# M105-bad.net
KiCad netlist of a schematic drawn in EAGLE
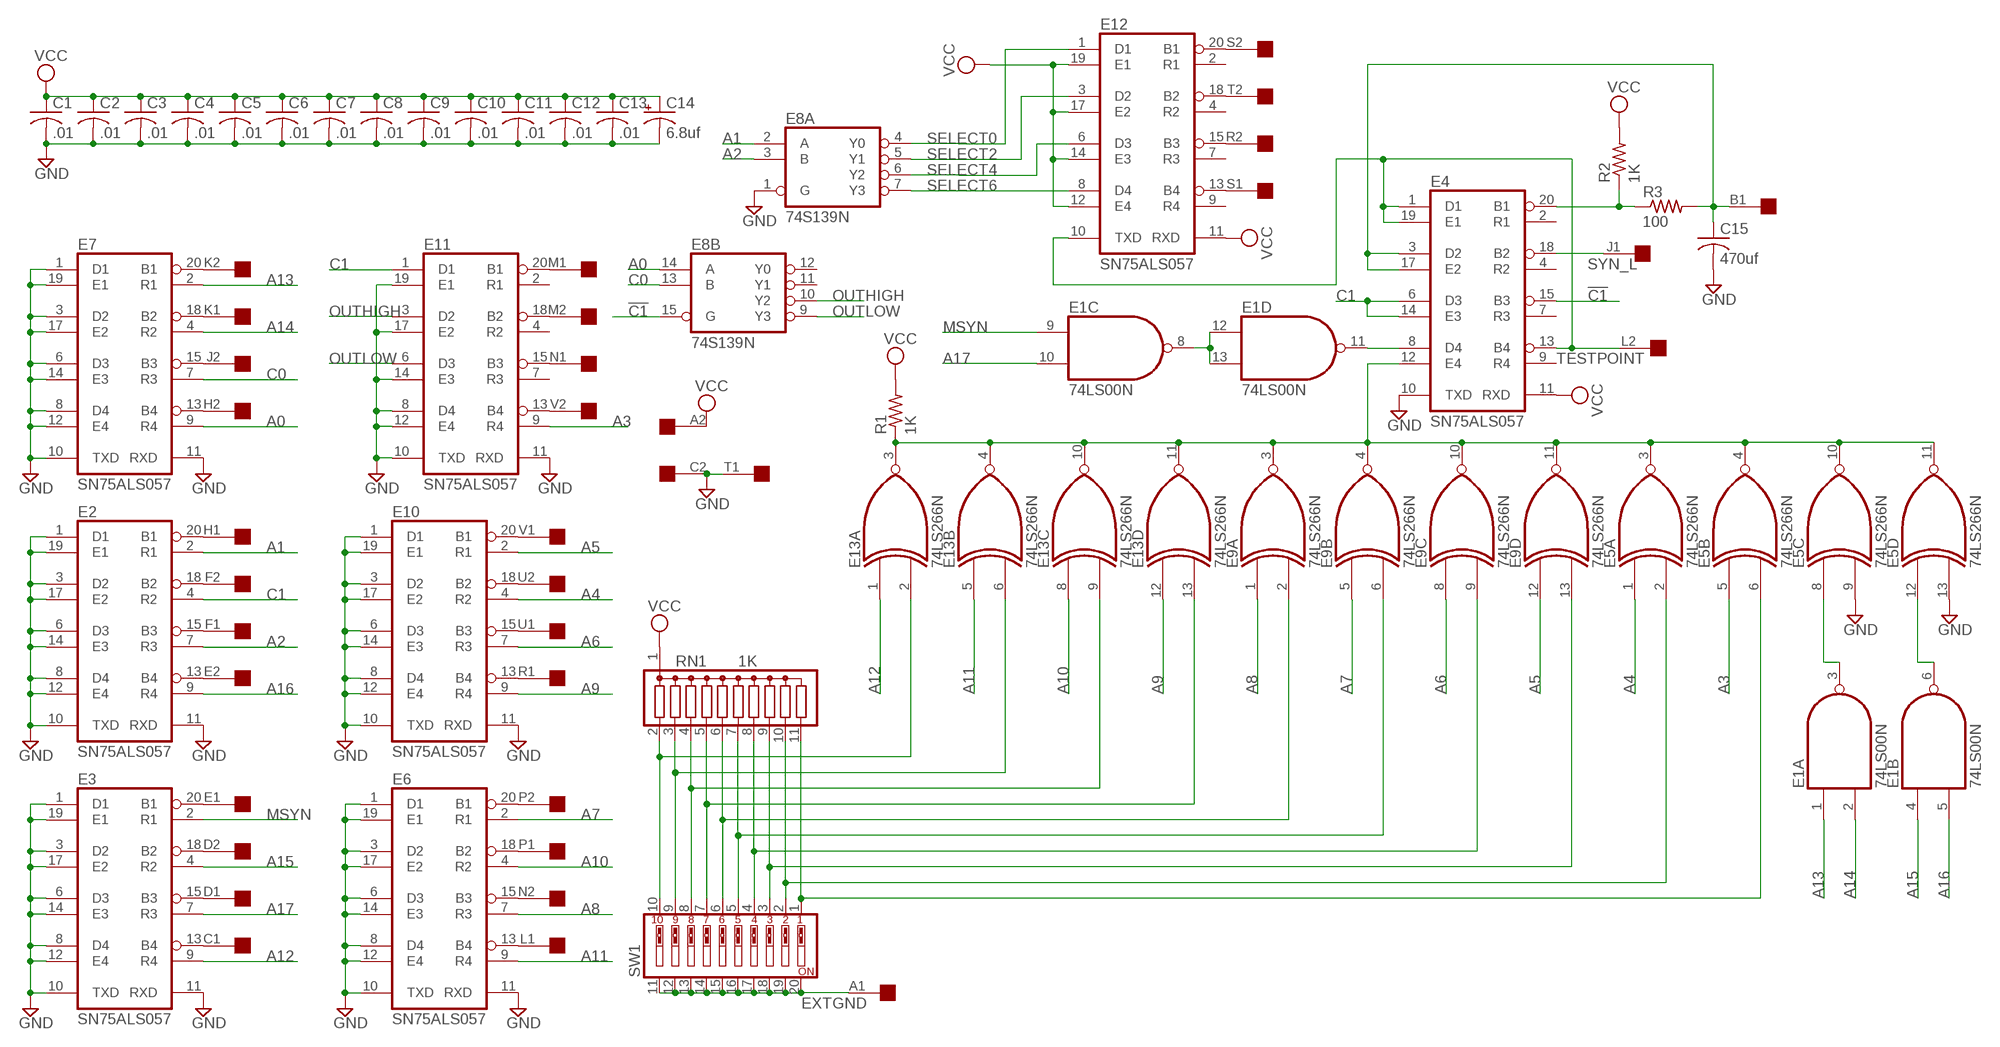
[diagram p0: schematic, sheet 1]

(export (version "E")
  (design (tool "Eeschema 10.0.6"))
  (components
    (comp (ref "C1")
      (value ".01")
      (footprint "eagle-import:C050-025X075")
      (libsource (lib "eagle-import") (part "C-US050-025X075"))
    )
    (comp (ref "C2")
      (value ".01")
      (footprint "eagle-import:C050-025X075")
      (libsource (lib "eagle-import") (part "C-US050-025X075"))
    )
    (comp (ref "C3")
      (value ".01")
      (footprint "eagle-import:C050-025X075")
      (libsource (lib "eagle-import") (part "C-US050-025X075"))
    )
    (comp (ref "C4")
      (value ".01")
      (footprint "eagle-import:C050-025X075")
      (libsource (lib "eagle-import") (part "C-US050-025X075"))
    )
    (comp (ref "C5")
      (value ".01")
      (footprint "eagle-import:C050-025X075")
      (libsource (lib "eagle-import") (part "C-US050-025X075"))
    )
    (comp (ref "C6")
      (value ".01")
      (footprint "eagle-import:C050-025X075")
      (libsource (lib "eagle-import") (part "C-US050-025X075"))
    )
    (comp (ref "C7")
      (value ".01")
      (footprint "eagle-import:C050-025X075")
      (libsource (lib "eagle-import") (part "C-US050-025X075"))
    )
    (comp (ref "C8")
      (value ".01")
      (footprint "eagle-import:C050-025X075")
      (libsource (lib "eagle-import") (part "C-US050-025X075"))
    )
    (comp (ref "C9")
      (value ".01")
      (footprint "eagle-import:C050-025X075")
      (libsource (lib "eagle-import") (part "C-US050-025X075"))
    )
    (comp (ref "C10")
      (value ".01")
      (footprint "eagle-import:C050-025X075")
      (libsource (lib "eagle-import") (part "C-US050-025X075"))
    )
    (comp (ref "C11")
      (value ".01")
      (footprint "eagle-import:C050-025X075")
      (libsource (lib "eagle-import") (part "C-US050-025X075"))
    )
    (comp (ref "C12")
      (value ".01")
      (footprint "eagle-import:C050-025X075")
      (libsource (lib "eagle-import") (part "C-US050-025X075"))
    )
    (comp (ref "C13")
      (value ".01")
      (footprint "eagle-import:C050-025X075")
      (libsource (lib "eagle-import") (part "C-US050-025X075"))
    )
    (comp (ref "C14")
      (value "6.8uf")
      (footprint "eagle-import:E15-5")
      (libsource (lib "eagle-import") (part "CPOL-USE15-5AXIAL"))
    )
    (comp (ref "C15")
      (value "470uf")
      (footprint "eagle-import:C050-025X075")
      (libsource (lib "eagle-import") (part "C-US050-025X075"))
    )
    (comp (ref "E1")
      (value "74LS00N")
      (footprint "eagle-import:DIL14")
      (libsource (lib "eagle-import") (part "7400NLS"))
    )
    (comp (ref "E2")
      (value "SN75ALS057")
      (footprint "eagle-import:DIL20")
      (libsource (lib "eagle-import") (part "SN75ALS057"))
    )
    (comp (ref "E3")
      (value "SN75ALS057")
      (footprint "eagle-import:DIL20")
      (libsource (lib "eagle-import") (part "SN75ALS057"))
    )
    (comp (ref "E4")
      (value "SN75ALS057")
      (footprint "eagle-import:DIL20")
      (libsource (lib "eagle-import") (part "SN75ALS057"))
    )
    (comp (ref "E5")
      (value "74LS266N")
      (footprint "eagle-import:DIL14")
      (libsource (lib "eagle-import") (part "74266NLS"))
    )
    (comp (ref "E6")
      (value "SN75ALS057")
      (footprint "eagle-import:DIL20")
      (libsource (lib "eagle-import") (part "SN75ALS057"))
    )
    (comp (ref "E7")
      (value "SN75ALS057")
      (footprint "eagle-import:DIL20")
      (libsource (lib "eagle-import") (part "SN75ALS057"))
    )
    (comp (ref "E8")
      (value "74S139N")
      (footprint "eagle-import:DIL16")
      (libsource (lib "eagle-import") (part "74139NS"))
    )
    (comp (ref "E9")
      (value "74LS266N")
      (footprint "eagle-import:DIL14")
      (libsource (lib "eagle-import") (part "74266NLS"))
    )
    (comp (ref "E10")
      (value "SN75ALS057")
      (footprint "eagle-import:DIL20")
      (libsource (lib "eagle-import") (part "SN75ALS057"))
    )
    (comp (ref "E11")
      (value "SN75ALS057")
      (footprint "eagle-import:DIL20")
      (libsource (lib "eagle-import") (part "SN75ALS057"))
    )
    (comp (ref "E12")
      (value "SN75ALS057")
      (footprint "eagle-import:DIL20")
      (libsource (lib "eagle-import") (part "SN75ALS057"))
    )
    (comp (ref "E13")
      (value "74LS266N")
      (footprint "eagle-import:DIL14")
      (libsource (lib "eagle-import") (part "74266NLS"))
    )
    (comp (ref "R1")
      (value "1K")
      (footprint "eagle-import:0207_10")
      (libsource (lib "eagle-import") (part "R-US_0207/10"))
    )
    (comp (ref "R2")
      (value "1K")
      (footprint "eagle-import:0207_10")
      (libsource (lib "eagle-import") (part "R-US_0207/10"))
    )
    (comp (ref "R3")
      (value "100")
      (footprint "eagle-import:0207_10")
      (libsource (lib "eagle-import") (part "R-US_0207/10"))
    )
    (comp (ref "RN1")
      (value "1K")
      (footprint "eagle-import:SIL11")
      (libsource (lib "eagle-import") (part "G10R"))
    )
    (comp (ref "SW1")
      (value "SW_DIP-10")
      (footprint "eagle-import:EDG-10")
      (libsource (lib "eagle-import") (part "SW_DIP-10"))
    )
    (comp (ref "U$1")
      (value "SINGLE")
      (footprint "eagle-import:EDGE-CON2")
      (libsource (lib "eagle-import") (part "SINGLE"))
    )
  )
  (nets
    (net (code "1") (name "/A0") (class "Default")
      (node (ref "E7") (pin "9") (pinfunction "R4_9") (pintype "output"))
      (node (ref "E8") (pin "14") (pinfunction "A_14") (pintype "input"))
    )
    (net (code "2") (name "/A1") (class "Default")
      (node (ref "E2") (pin "2") (pinfunction "R1_2") (pintype "output"))
      (node (ref "E8") (pin "2") (pinfunction "A_2") (pintype "input"))
    )
    (net (code "3") (name "/A2") (class "Default")
      (node (ref "E2") (pin "7") (pinfunction "R3_7") (pintype "output"))
      (node (ref "E8") (pin "3") (pinfunction "B_3") (pintype "input"))
    )
    (net (code "4") (name "/A3") (class "Default")
      (node (ref "E11") (pin "9") (pinfunction "R4_9") (pintype "output"))
      (node (ref "E5") (pin "5") (pinfunction "I0_5") (pintype "input"))
    )
    (net (code "5") (name "/A4") (class "Default")
      (node (ref "E10") (pin "4") (pinfunction "R2_4") (pintype "output"))
      (node (ref "E5") (pin "1") (pinfunction "I0_1") (pintype "input"))
    )
    (net (code "6") (name "/A5") (class "Default")
      (node (ref "E10") (pin "2") (pinfunction "R1_2") (pintype "output"))
      (node (ref "E9") (pin "12") (pinfunction "I0_12") (pintype "input"))
    )
    (net (code "7") (name "/A6") (class "Default")
      (node (ref "E10") (pin "7") (pinfunction "R3_7") (pintype "output"))
      (node (ref "E9") (pin "8") (pinfunction "I0_8") (pintype "input"))
    )
    (net (code "8") (name "/A7") (class "Default")
      (node (ref "E6") (pin "2") (pinfunction "R1_2") (pintype "output"))
      (node (ref "E9") (pin "5") (pinfunction "I0_5") (pintype "input"))
    )
    (net (code "9") (name "/A8") (class "Default")
      (node (ref "E6") (pin "7") (pinfunction "R3_7") (pintype "output"))
      (node (ref "E9") (pin "1") (pinfunction "I0_1") (pintype "input"))
    )
    (net (code "10") (name "/A9") (class "Default")
      (node (ref "E10") (pin "9") (pinfunction "R4_9") (pintype "output"))
      (node (ref "E13") (pin "12") (pinfunction "I0_12") (pintype "input"))
    )
    (net (code "11") (name "/A10") (class "Default")
      (node (ref "E13") (pin "8") (pinfunction "I0_8") (pintype "input"))
      (node (ref "E6") (pin "4") (pinfunction "R2_4") (pintype "output"))
    )
    (net (code "12") (name "/A11") (class "Default")
      (node (ref "E13") (pin "5") (pinfunction "I0_5") (pintype "input"))
      (node (ref "E6") (pin "9") (pinfunction "R4_9") (pintype "output"))
    )
    (net (code "13") (name "/A12") (class "Default")
      (node (ref "E13") (pin "1") (pinfunction "I0_1") (pintype "input"))
      (node (ref "E3") (pin "9") (pinfunction "R4_9") (pintype "output"))
    )
    (net (code "14") (name "/A13") (class "Default")
      (node (ref "E1") (pin "1") (pinfunction "I0_1") (pintype "input"))
      (node (ref "E7") (pin "2") (pinfunction "R1_2") (pintype "output"))
    )
    (net (code "15") (name "/A14") (class "Default")
      (node (ref "E1") (pin "2") (pinfunction "I1_2") (pintype "input"))
      (node (ref "E7") (pin "4") (pinfunction "R2_4") (pintype "output"))
    )
    (net (code "16") (name "/A15") (class "Default")
      (node (ref "E1") (pin "4") (pinfunction "I0_4") (pintype "input"))
      (node (ref "E3") (pin "4") (pinfunction "R2_4") (pintype "output"))
    )
    (net (code "17") (name "/A16") (class "Default")
      (node (ref "E1") (pin "5") (pinfunction "I1_5") (pintype "input"))
      (node (ref "E2") (pin "9") (pinfunction "R4_9") (pintype "output"))
    )
    (net (code "18") (name "/A17") (class "Default")
      (node (ref "E1") (pin "10") (pinfunction "I1_10") (pintype "input"))
      (node (ref "E3") (pin "7") (pinfunction "R3_7") (pintype "output"))
    )
    (net (code "19") (name "/C0") (class "Default")
      (node (ref "E7") (pin "7") (pinfunction "R3_7") (pintype "output"))
      (node (ref "E8") (pin "13") (pinfunction "B_13") (pintype "input"))
    )
    (net (code "20") (name "/C1") (class "Default")
      (node (ref "E11") (pin "1") (pinfunction "D1_1") (pintype "input"))
      (node (ref "E2") (pin "4") (pinfunction "R2_4") (pintype "output"))
      (node (ref "E4") (pin "14") (pinfunction "E3_14") (pintype "input"))
      (node (ref "E4") (pin "6") (pinfunction "D3_6") (pintype "input"))
    )
    (net (code "21") (name "/EXTGND") (class "Default")
      (node (ref "SW1") (pin "11") (pinfunction "11_11") (pintype "passive"))
      (node (ref "SW1") (pin "12") (pinfunction "12_12") (pintype "passive"))
      (node (ref "SW1") (pin "13") (pinfunction "13_13") (pintype "passive"))
      (node (ref "SW1") (pin "14") (pinfunction "14_14") (pintype "passive"))
      (node (ref "SW1") (pin "15") (pinfunction "15_15") (pintype "passive"))
      (node (ref "SW1") (pin "16") (pinfunction "16_16") (pintype "passive"))
      (node (ref "SW1") (pin "17") (pinfunction "17_17") (pintype "passive"))
      (node (ref "SW1") (pin "18") (pinfunction "18_18") (pintype "passive"))
      (node (ref "SW1") (pin "19") (pinfunction "19_19") (pintype "passive"))
      (node (ref "SW1") (pin "20") (pinfunction "20_20") (pintype "passive"))
      (node (ref "U$1") (pin "A1") (pinfunction "1_A1") (pintype "bidirectional"))
    )
    (net (code "22") (name "/MSYN") (class "Default")
      (node (ref "E1") (pin "9") (pinfunction "I0_9") (pintype "input"))
      (node (ref "E3") (pin "2") (pinfunction "R1_2") (pintype "output"))
    )
    (net (code "23") (name "/OUTHIGH") (class "Default")
      (node (ref "E11") (pin "3") (pinfunction "D2_3") (pintype "input"))
      (node (ref "E8") (pin "10") (pinfunction "Y2_10") (pintype "output"))
    )
    (net (code "24") (name "/OUTLOW") (class "Default")
      (node (ref "E11") (pin "6") (pinfunction "D3_6") (pintype "input"))
      (node (ref "E8") (pin "9") (pinfunction "Y3_9") (pintype "output"))
    )
    (net (code "25") (name "/SELECT0") (class "Default")
      (node (ref "E12") (pin "1") (pinfunction "D1_1") (pintype "input"))
      (node (ref "E8") (pin "4") (pinfunction "Y0_4") (pintype "output"))
    )
    (net (code "26") (name "/SELECT2") (class "Default")
      (node (ref "E12") (pin "3") (pinfunction "D2_3") (pintype "input"))
      (node (ref "E8") (pin "5") (pinfunction "Y1_5") (pintype "output"))
    )
    (net (code "27") (name "/SELECT4") (class "Default")
      (node (ref "E12") (pin "6") (pinfunction "D3_6") (pintype "input"))
      (node (ref "E8") (pin "6") (pinfunction "Y2_6") (pintype "output"))
    )
    (net (code "28") (name "/SELECT6") (class "Default")
      (node (ref "E12") (pin "8") (pinfunction "D4_8") (pintype "input"))
      (node (ref "E8") (pin "7") (pinfunction "Y3_7") (pintype "output"))
    )
    (net (code "29") (name "/SYN_L") (class "Default")
      (node (ref "E4") (pin "18") (pinfunction "B2_18") (pintype "bidirectional"))
      (node (ref "U$1") (pin "J1") (pinfunction "1_J1") (pintype "bidirectional"))
    )
    (net (code "30") (name "/TESTPOINT") (class "Default")
      (node (ref "E12") (pin "10") (pinfunction "TXD_10") (pintype "input"))
      (node (ref "E4") (pin "1") (pinfunction "D1_1") (pintype "input"))
      (node (ref "E4") (pin "13") (pinfunction "B4_13") (pintype "bidirectional"))
      (node (ref "E4") (pin "19") (pinfunction "E1_19") (pintype "input"))
      (node (ref "U$1") (pin "L2") (pinfunction "1_L2") (pintype "bidirectional"))
    )
    (net (code "31") (name "/~{C1}") (class "Default")
      (node (ref "E4") (pin "15") (pinfunction "B3_15") (pintype "bidirectional"))
      (node (ref "E8") (pin "15") (pinfunction "G_15") (pintype "input"))
    )
    (net (code "32") (name "GND") (class "Default")
      (node (ref "C1") (pin "2") (pinfunction "2_2") (pintype "passive"))
      (node (ref "C10") (pin "2") (pinfunction "2_2") (pintype "passive"))
      (node (ref "C11") (pin "2") (pinfunction "2_2") (pintype "passive"))
      (node (ref "C12") (pin "2") (pinfunction "2_2") (pintype "passive"))
      (node (ref "C13") (pin "2") (pinfunction "2_2") (pintype "passive"))
      (node (ref "C14") (pin "-") (pinfunction "-_-") (pintype "passive"))
      (node (ref "C15") (pin "2") (pinfunction "2_2") (pintype "passive"))
      (node (ref "C2") (pin "2") (pinfunction "2_2") (pintype "passive"))
      (node (ref "C3") (pin "2") (pinfunction "2_2") (pintype "passive"))
      (node (ref "C4") (pin "2") (pinfunction "2_2") (pintype "passive"))
      (node (ref "C5") (pin "2") (pinfunction "2_2") (pintype "passive"))
      (node (ref "C6") (pin "2") (pinfunction "2_2") (pintype "passive"))
      (node (ref "C7") (pin "2") (pinfunction "2_2") (pintype "passive"))
      (node (ref "C8") (pin "2") (pinfunction "2_2") (pintype "passive"))
      (node (ref "C9") (pin "2") (pinfunction "2_2") (pintype "passive"))
      (node (ref "E10") (pin "1") (pinfunction "D1_1") (pintype "input"))
      (node (ref "E10") (pin "10") (pinfunction "TXD_10") (pintype "input"))
      (node (ref "E10") (pin "11") (pinfunction "RXD_11") (pintype "input"))
      (node (ref "E10") (pin "12") (pinfunction "E4_12") (pintype "input"))
      (node (ref "E10") (pin "14") (pinfunction "E3_14") (pintype "input"))
      (node (ref "E10") (pin "17") (pinfunction "E2_17") (pintype "input"))
      (node (ref "E10") (pin "19") (pinfunction "E1_19") (pintype "input"))
      (node (ref "E10") (pin "3") (pinfunction "D2_3") (pintype "input"))
      (node (ref "E10") (pin "6") (pinfunction "D3_6") (pintype "input"))
      (node (ref "E10") (pin "8") (pinfunction "D4_8") (pintype "input"))
      (node (ref "E11") (pin "10") (pinfunction "TXD_10") (pintype "input"))
      (node (ref "E11") (pin "11") (pinfunction "RXD_11") (pintype "input"))
      (node (ref "E11") (pin "12") (pinfunction "E4_12") (pintype "input"))
      (node (ref "E11") (pin "14") (pinfunction "E3_14") (pintype "input"))
      (node (ref "E11") (pin "17") (pinfunction "E2_17") (pintype "input"))
      (node (ref "E11") (pin "19") (pinfunction "E1_19") (pintype "input"))
      (node (ref "E11") (pin "8") (pinfunction "D4_8") (pintype "input"))
      (node (ref "E2") (pin "1") (pinfunction "D1_1") (pintype "input"))
      (node (ref "E2") (pin "10") (pinfunction "TXD_10") (pintype "input"))
      (node (ref "E2") (pin "11") (pinfunction "RXD_11") (pintype "input"))
      (node (ref "E2") (pin "12") (pinfunction "E4_12") (pintype "input"))
      (node (ref "E2") (pin "14") (pinfunction "E3_14") (pintype "input"))
      (node (ref "E2") (pin "17") (pinfunction "E2_17") (pintype "input"))
      (node (ref "E2") (pin "19") (pinfunction "E1_19") (pintype "input"))
      (node (ref "E2") (pin "3") (pinfunction "D2_3") (pintype "input"))
      (node (ref "E2") (pin "6") (pinfunction "D3_6") (pintype "input"))
      (node (ref "E2") (pin "8") (pinfunction "D4_8") (pintype "input"))
      (node (ref "E3") (pin "1") (pinfunction "D1_1") (pintype "input"))
      (node (ref "E3") (pin "10") (pinfunction "TXD_10") (pintype "input"))
      (node (ref "E3") (pin "11") (pinfunction "RXD_11") (pintype "input"))
      (node (ref "E3") (pin "12") (pinfunction "E4_12") (pintype "input"))
      (node (ref "E3") (pin "14") (pinfunction "E3_14") (pintype "input"))
      (node (ref "E3") (pin "17") (pinfunction "E2_17") (pintype "input"))
      (node (ref "E3") (pin "19") (pinfunction "E1_19") (pintype "input"))
      (node (ref "E3") (pin "3") (pinfunction "D2_3") (pintype "input"))
      (node (ref "E3") (pin "6") (pinfunction "D3_6") (pintype "input"))
      (node (ref "E3") (pin "8") (pinfunction "D4_8") (pintype "input"))
      (node (ref "E4") (pin "10") (pinfunction "TXD_10") (pintype "input"))
      (node (ref "E5") (pin "13") (pinfunction "I1_13") (pintype "input"))
      (node (ref "E5") (pin "9") (pinfunction "I1_9") (pintype "input"))
      (node (ref "E6") (pin "1") (pinfunction "D1_1") (pintype "input"))
      (node (ref "E6") (pin "10") (pinfunction "TXD_10") (pintype "input"))
      (node (ref "E6") (pin "11") (pinfunction "RXD_11") (pintype "input"))
      (node (ref "E6") (pin "12") (pinfunction "E4_12") (pintype "input"))
      (node (ref "E6") (pin "14") (pinfunction "E3_14") (pintype "input"))
      (node (ref "E6") (pin "17") (pinfunction "E2_17") (pintype "input"))
      (node (ref "E6") (pin "19") (pinfunction "E1_19") (pintype "input"))
      (node (ref "E6") (pin "3") (pinfunction "D2_3") (pintype "input"))
      (node (ref "E6") (pin "6") (pinfunction "D3_6") (pintype "input"))
      (node (ref "E6") (pin "8") (pinfunction "D4_8") (pintype "input"))
      (node (ref "E7") (pin "1") (pinfunction "D1_1") (pintype "input"))
      (node (ref "E7") (pin "10") (pinfunction "TXD_10") (pintype "input"))
      (node (ref "E7") (pin "11") (pinfunction "RXD_11") (pintype "input"))
      (node (ref "E7") (pin "12") (pinfunction "E4_12") (pintype "input"))
      (node (ref "E7") (pin "14") (pinfunction "E3_14") (pintype "input"))
      (node (ref "E7") (pin "17") (pinfunction "E2_17") (pintype "input"))
      (node (ref "E7") (pin "19") (pinfunction "E1_19") (pintype "input"))
      (node (ref "E7") (pin "3") (pinfunction "D2_3") (pintype "input"))
      (node (ref "E7") (pin "6") (pinfunction "D3_6") (pintype "input"))
      (node (ref "E7") (pin "8") (pinfunction "D4_8") (pintype "input"))
      (node (ref "E8") (pin "1") (pinfunction "G_1") (pintype "input"))
      (node (ref "U$1") (pin "C2") (pinfunction "1_C2") (pintype "bidirectional"))
      (node (ref "U$1") (pin "T1") (pinfunction "1_T1") (pintype "bidirectional"))
    )
    (net (code "33") (name "Net-(E1A-O)") (class "Default")
      (node (ref "E1") (pin "3") (pinfunction "O_3") (pintype "output"))
      (node (ref "E5") (pin "8") (pinfunction "I0_8") (pintype "input"))
    )
    (net (code "34") (name "Net-(E1B-O)") (class "Default")
      (node (ref "E1") (pin "6") (pinfunction "O_6") (pintype "output"))
      (node (ref "E5") (pin "12") (pinfunction "I0_12") (pintype "input"))
    )
    (net (code "35") (name "Net-(E1C-O)") (class "Default")
      (node (ref "E1") (pin "12") (pinfunction "I0_12") (pintype "input"))
      (node (ref "E1") (pin "13") (pinfunction "I1_13") (pintype "input"))
      (node (ref "E1") (pin "8") (pinfunction "O_8") (pintype "output"))
    )
    (net (code "36") (name "Net-(E1D-O)") (class "Default")
      (node (ref "E1") (pin "11") (pinfunction "O_11") (pintype "output"))
      (node (ref "E4") (pin "8") (pinfunction "D4_8") (pintype "input"))
    )
    (net (code "37") (name "Net-(E2A-B1)") (class "Default")
      (node (ref "E2") (pin "20") (pinfunction "B1_20") (pintype "bidirectional"))
      (node (ref "U$1") (pin "H1") (pinfunction "1_H1") (pintype "bidirectional"))
    )
    (net (code "38") (name "Net-(E2A-B2)") (class "Default")
      (node (ref "E2") (pin "18") (pinfunction "B2_18") (pintype "bidirectional"))
      (node (ref "U$1") (pin "F2") (pinfunction "1_F2") (pintype "bidirectional"))
    )
    (net (code "39") (name "Net-(E2A-B3)") (class "Default")
      (node (ref "E2") (pin "15") (pinfunction "B3_15") (pintype "bidirectional"))
      (node (ref "U$1") (pin "F1") (pinfunction "1_F1") (pintype "bidirectional"))
    )
    (net (code "40") (name "Net-(E2A-B4)") (class "Default")
      (node (ref "E2") (pin "13") (pinfunction "B4_13") (pintype "bidirectional"))
      (node (ref "U$1") (pin "E2") (pinfunction "1_E2") (pintype "bidirectional"))
    )
    (net (code "41") (name "Net-(E3A-B1)") (class "Default")
      (node (ref "E3") (pin "20") (pinfunction "B1_20") (pintype "bidirectional"))
      (node (ref "U$1") (pin "E1") (pinfunction "1_E1") (pintype "bidirectional"))
    )
    (net (code "42") (name "Net-(E3A-B2)") (class "Default")
      (node (ref "E3") (pin "18") (pinfunction "B2_18") (pintype "bidirectional"))
      (node (ref "U$1") (pin "D2") (pinfunction "1_D2") (pintype "bidirectional"))
    )
    (net (code "43") (name "Net-(E3A-B3)") (class "Default")
      (node (ref "E3") (pin "15") (pinfunction "B3_15") (pintype "bidirectional"))
      (node (ref "U$1") (pin "D1") (pinfunction "1_D1") (pintype "bidirectional"))
    )
    (net (code "44") (name "Net-(E3A-B4)") (class "Default")
      (node (ref "E3") (pin "13") (pinfunction "B4_13") (pintype "bidirectional"))
      (node (ref "U$1") (pin "C1") (pinfunction "1_C1") (pintype "bidirectional"))
    )
    (net (code "45") (name "Net-(E4A-B1)") (class "Default")
      (node (ref "E4") (pin "20") (pinfunction "B1_20") (pintype "bidirectional"))
      (node (ref "R2") (pin "1") (pinfunction "1_1") (pintype "passive"))
      (node (ref "R3") (pin "1") (pinfunction "1_1") (pintype "passive"))
    )
    (net (code "46") (name "Net-(E4A-D2)") (class "Default")
      (node (ref "C15") (pin "1") (pinfunction "1_1") (pintype "passive"))
      (node (ref "E4") (pin "17") (pinfunction "E2_17") (pintype "input"))
      (node (ref "E4") (pin "3") (pinfunction "D2_3") (pintype "input"))
      (node (ref "R3") (pin "2") (pinfunction "2_2") (pintype "passive"))
      (node (ref "U$1") (pin "B1") (pinfunction "1_B1") (pintype "bidirectional"))
    )
    (net (code "47") (name "Net-(E5A-I1)") (class "Default")
      (node (ref "E5") (pin "2") (pinfunction "I1_2") (pintype "input"))
      (node (ref "RN1") (pin "10") (pinfunction "10_10") (pintype "passive"))
      (node (ref "SW1") (pin "2") (pinfunction "2_2") (pintype "passive"))
    )
    (net (code "48") (name "Net-(E5B-I1)") (class "Default")
      (node (ref "E5") (pin "6") (pinfunction "I1_6") (pintype "input"))
      (node (ref "RN1") (pin "11") (pinfunction "11_11") (pintype "passive"))
      (node (ref "SW1") (pin "1") (pinfunction "1_1") (pintype "passive"))
    )
    (net (code "49") (name "Net-(E6A-B1)") (class "Default")
      (node (ref "E6") (pin "20") (pinfunction "B1_20") (pintype "bidirectional"))
      (node (ref "U$1") (pin "P2") (pinfunction "1_P2") (pintype "bidirectional"))
    )
    (net (code "50") (name "Net-(E6A-B2)") (class "Default")
      (node (ref "E6") (pin "18") (pinfunction "B2_18") (pintype "bidirectional"))
      (node (ref "U$1") (pin "P1") (pinfunction "1_P1") (pintype "bidirectional"))
    )
    (net (code "51") (name "Net-(E6A-B3)") (class "Default")
      (node (ref "E6") (pin "15") (pinfunction "B3_15") (pintype "bidirectional"))
      (node (ref "U$1") (pin "N2") (pinfunction "1_N2") (pintype "bidirectional"))
    )
    (net (code "52") (name "Net-(E6A-B4)") (class "Default")
      (node (ref "E6") (pin "13") (pinfunction "B4_13") (pintype "bidirectional"))
      (node (ref "U$1") (pin "L1") (pinfunction "1_L1") (pintype "bidirectional"))
    )
    (net (code "53") (name "Net-(E7A-B1)") (class "Default")
      (node (ref "E7") (pin "20") (pinfunction "B1_20") (pintype "bidirectional"))
      (node (ref "U$1") (pin "K2") (pinfunction "1_K2") (pintype "bidirectional"))
    )
    (net (code "54") (name "Net-(E7A-B2)") (class "Default")
      (node (ref "E7") (pin "18") (pinfunction "B2_18") (pintype "bidirectional"))
      (node (ref "U$1") (pin "K1") (pinfunction "1_K1") (pintype "bidirectional"))
    )
    (net (code "55") (name "Net-(E7A-B3)") (class "Default")
      (node (ref "E7") (pin "15") (pinfunction "B3_15") (pintype "bidirectional"))
      (node (ref "U$1") (pin "J2") (pinfunction "1_J2") (pintype "bidirectional"))
    )
    (net (code "56") (name "Net-(E7A-B4)") (class "Default")
      (node (ref "E7") (pin "13") (pinfunction "B4_13") (pintype "bidirectional"))
      (node (ref "U$1") (pin "H2") (pinfunction "1_H2") (pintype "bidirectional"))
    )
    (net (code "57") (name "Net-(E9A-I1)") (class "Default")
      (node (ref "E9") (pin "2") (pinfunction "I1_2") (pintype "input"))
      (node (ref "RN1") (pin "6") (pinfunction "6_6") (pintype "passive"))
      (node (ref "SW1") (pin "6") (pinfunction "6_6") (pintype "passive"))
    )
    (net (code "58") (name "Net-(E9B-I1)") (class "Default")
      (node (ref "E9") (pin "6") (pinfunction "I1_6") (pintype "input"))
      (node (ref "RN1") (pin "7") (pinfunction "7_7") (pintype "passive"))
      (node (ref "SW1") (pin "5") (pinfunction "5_5") (pintype "passive"))
    )
    (net (code "59") (name "Net-(E9C-I1)") (class "Default")
      (node (ref "E9") (pin "9") (pinfunction "I1_9") (pintype "input"))
      (node (ref "RN1") (pin "8") (pinfunction "8_8") (pintype "passive"))
      (node (ref "SW1") (pin "4") (pinfunction "4_4") (pintype "passive"))
    )
    (net (code "60") (name "Net-(E9D-I1)") (class "Default")
      (node (ref "E9") (pin "13") (pinfunction "I1_13") (pintype "input"))
      (node (ref "RN1") (pin "9") (pinfunction "9_9") (pintype "passive"))
      (node (ref "SW1") (pin "3") (pinfunction "3_3") (pintype "passive"))
    )
    (net (code "61") (name "Net-(E10A-B1)") (class "Default")
      (node (ref "E10") (pin "20") (pinfunction "B1_20") (pintype "bidirectional"))
      (node (ref "U$1") (pin "V1") (pinfunction "1_V1") (pintype "bidirectional"))
    )
    (net (code "62") (name "Net-(E10A-B2)") (class "Default")
      (node (ref "E10") (pin "18") (pinfunction "B2_18") (pintype "bidirectional"))
      (node (ref "U$1") (pin "U2") (pinfunction "1_U2") (pintype "bidirectional"))
    )
    (net (code "63") (name "Net-(E10A-B3)") (class "Default")
      (node (ref "E10") (pin "15") (pinfunction "B3_15") (pintype "bidirectional"))
      (node (ref "U$1") (pin "U1") (pinfunction "1_U1") (pintype "bidirectional"))
    )
    (net (code "64") (name "Net-(E10A-B4)") (class "Default")
      (node (ref "E10") (pin "13") (pinfunction "B4_13") (pintype "bidirectional"))
      (node (ref "U$1") (pin "R1") (pinfunction "1_R1") (pintype "bidirectional"))
    )
    (net (code "65") (name "Net-(E11A-B1)") (class "Default")
      (node (ref "E11") (pin "20") (pinfunction "B1_20") (pintype "bidirectional"))
      (node (ref "U$1") (pin "M1") (pinfunction "1_M1") (pintype "bidirectional"))
    )
    (net (code "66") (name "Net-(E11A-B2)") (class "Default")
      (node (ref "E11") (pin "18") (pinfunction "B2_18") (pintype "bidirectional"))
      (node (ref "U$1") (pin "M2") (pinfunction "1_M2") (pintype "bidirectional"))
    )
    (net (code "67") (name "Net-(E11A-B3)") (class "Default")
      (node (ref "E11") (pin "15") (pinfunction "B3_15") (pintype "bidirectional"))
      (node (ref "U$1") (pin "N1") (pinfunction "1_N1") (pintype "bidirectional"))
    )
    (net (code "68") (name "Net-(E11A-B4)") (class "Default")
      (node (ref "E11") (pin "13") (pinfunction "B4_13") (pintype "bidirectional"))
      (node (ref "U$1") (pin "V2") (pinfunction "1_V2") (pintype "bidirectional"))
    )
    (net (code "69") (name "Net-(E12A-B1)") (class "Default")
      (node (ref "E12") (pin "20") (pinfunction "B1_20") (pintype "bidirectional"))
      (node (ref "U$1") (pin "S2") (pinfunction "1_S2") (pintype "bidirectional"))
    )
    (net (code "70") (name "Net-(E12A-B2)") (class "Default")
      (node (ref "E12") (pin "18") (pinfunction "B2_18") (pintype "bidirectional"))
      (node (ref "U$1") (pin "T2") (pinfunction "1_T2") (pintype "bidirectional"))
    )
    (net (code "71") (name "Net-(E12A-B3)") (class "Default")
      (node (ref "E12") (pin "15") (pinfunction "B3_15") (pintype "bidirectional"))
      (node (ref "U$1") (pin "R2") (pinfunction "1_R2") (pintype "bidirectional"))
    )
    (net (code "72") (name "Net-(E12A-B4)") (class "Default")
      (node (ref "E12") (pin "13") (pinfunction "B4_13") (pintype "bidirectional"))
      (node (ref "U$1") (pin "S1") (pinfunction "1_S1") (pintype "bidirectional"))
    )
    (net (code "73") (name "Net-(E13A-I1)") (class "Default")
      (node (ref "E13") (pin "2") (pinfunction "I1_2") (pintype "input"))
      (node (ref "RN1") (pin "2") (pinfunction "2_2") (pintype "passive"))
      (node (ref "SW1") (pin "10") (pinfunction "10_10") (pintype "passive"))
    )
    (net (code "74") (name "Net-(E13A-O)") (class "Default")
      (node (ref "E13") (pin "10") (pinfunction "O_10") (pintype "open_collector"))
      (node (ref "E13") (pin "11") (pinfunction "O_11") (pintype "open_collector"))
      (node (ref "E13") (pin "3") (pinfunction "O_3") (pintype "open_collector"))
      (node (ref "E13") (pin "4") (pinfunction "O_4") (pintype "open_collector"))
      (node (ref "E4") (pin "12") (pinfunction "E4_12") (pintype "input"))
      (node (ref "E5") (pin "10") (pinfunction "O_10") (pintype "open_collector"))
      (node (ref "E5") (pin "11") (pinfunction "O_11") (pintype "open_collector"))
      (node (ref "E5") (pin "3") (pinfunction "O_3") (pintype "open_collector"))
      (node (ref "E5") (pin "4") (pinfunction "O_4") (pintype "open_collector"))
      (node (ref "E9") (pin "10") (pinfunction "O_10") (pintype "open_collector"))
      (node (ref "E9") (pin "11") (pinfunction "O_11") (pintype "open_collector"))
      (node (ref "E9") (pin "3") (pinfunction "O_3") (pintype "open_collector"))
      (node (ref "E9") (pin "4") (pinfunction "O_4") (pintype "open_collector"))
      (node (ref "R1") (pin "1") (pinfunction "1_1") (pintype "passive"))
    )
    (net (code "75") (name "Net-(E13B-I1)") (class "Default")
      (node (ref "E13") (pin "6") (pinfunction "I1_6") (pintype "input"))
      (node (ref "RN1") (pin "3") (pinfunction "3_3") (pintype "passive"))
      (node (ref "SW1") (pin "9") (pinfunction "9_9") (pintype "passive"))
    )
    (net (code "76") (name "Net-(E13C-I1)") (class "Default")
      (node (ref "E13") (pin "9") (pinfunction "I1_9") (pintype "input"))
      (node (ref "RN1") (pin "4") (pinfunction "4_4") (pintype "passive"))
      (node (ref "SW1") (pin "8") (pinfunction "8_8") (pintype "passive"))
    )
    (net (code "77") (name "Net-(E13D-I1)") (class "Default")
      (node (ref "E13") (pin "13") (pinfunction "I1_13") (pintype "input"))
      (node (ref "RN1") (pin "5") (pinfunction "5_5") (pintype "passive"))
      (node (ref "SW1") (pin "7") (pinfunction "7_7") (pintype "passive"))
    )
    (net (code "78") (name "VCC") (class "Default")
      (node (ref "C1") (pin "1") (pinfunction "1_1") (pintype "passive"))
      (node (ref "C10") (pin "1") (pinfunction "1_1") (pintype "passive"))
      (node (ref "C11") (pin "1") (pinfunction "1_1") (pintype "passive"))
      (node (ref "C12") (pin "1") (pinfunction "1_1") (pintype "passive"))
      (node (ref "C13") (pin "1") (pinfunction "1_1") (pintype "passive"))
      (node (ref "C14") (pin "+") (pinfunction "+_+") (pintype "passive"))
      (node (ref "C2") (pin "1") (pinfunction "1_1") (pintype "passive"))
      (node (ref "C3") (pin "1") (pinfunction "1_1") (pintype "passive"))
      (node (ref "C4") (pin "1") (pinfunction "1_1") (pintype "passive"))
      (node (ref "C5") (pin "1") (pinfunction "1_1") (pintype "passive"))
      (node (ref "C6") (pin "1") (pinfunction "1_1") (pintype "passive"))
      (node (ref "C7") (pin "1") (pinfunction "1_1") (pintype "passive"))
      (node (ref "C8") (pin "1") (pinfunction "1_1") (pintype "passive"))
      (node (ref "C9") (pin "1") (pinfunction "1_1") (pintype "passive"))
      (node (ref "E12") (pin "11") (pinfunction "RXD_11") (pintype "input"))
      (node (ref "E12") (pin "12") (pinfunction "E4_12") (pintype "input"))
      (node (ref "E12") (pin "14") (pinfunction "E3_14") (pintype "input"))
      (node (ref "E12") (pin "17") (pinfunction "E2_17") (pintype "input"))
      (node (ref "E12") (pin "19") (pinfunction "E1_19") (pintype "input"))
      (node (ref "E4") (pin "11") (pinfunction "RXD_11") (pintype "input"))
      (node (ref "R1") (pin "2") (pinfunction "2_2") (pintype "passive"))
      (node (ref "R2") (pin "2") (pinfunction "2_2") (pintype "passive"))
      (node (ref "RN1") (pin "1") (pinfunction "1_1") (pintype "passive"))
      (node (ref "U$1") (pin "A2") (pinfunction "1_A2") (pintype "bidirectional"))
    )
    (net (code "79") (name "unconnected-(E4A-R1-Pad2)") (class "Default")
      (node (ref "E4") (pin "2") (pinfunction "R1_2") (pintype "output"))
    )
    (net (code "80") (name "unconnected-(E4A-R2-Pad4)") (class "Default")
      (node (ref "E4") (pin "4") (pinfunction "R2_4") (pintype "output"))
    )
    (net (code "81") (name "unconnected-(E4A-R3-Pad7)") (class "Default")
      (node (ref "E4") (pin "7") (pinfunction "R3_7") (pintype "output"))
    )
    (net (code "82") (name "unconnected-(E4A-R4-Pad9)") (class "Default")
      (node (ref "E4") (pin "9") (pinfunction "R4_9") (pintype "output"))
    )
    (net (code "83") (name "unconnected-(E8B-Y0-Pad12)") (class "Default")
      (node (ref "E8") (pin "12") (pinfunction "Y0_12") (pintype "output"))
    )
    (net (code "84") (name "unconnected-(E8B-Y1-Pad11)") (class "Default")
      (node (ref "E8") (pin "11") (pinfunction "Y1_11") (pintype "output"))
    )
    (net (code "85") (name "unconnected-(E11A-R1-Pad2)") (class "Default")
      (node (ref "E11") (pin "2") (pinfunction "R1_2") (pintype "output"))
    )
    (net (code "86") (name "unconnected-(E11A-R2-Pad4)") (class "Default")
      (node (ref "E11") (pin "4") (pinfunction "R2_4") (pintype "output"))
    )
    (net (code "87") (name "unconnected-(E11A-R3-Pad7)") (class "Default")
      (node (ref "E11") (pin "7") (pinfunction "R3_7") (pintype "output"))
    )
    (net (code "88") (name "unconnected-(E12A-R1-Pad2)") (class "Default")
      (node (ref "E12") (pin "2") (pinfunction "R1_2") (pintype "output"))
    )
    (net (code "89") (name "unconnected-(E12A-R2-Pad4)") (class "Default")
      (node (ref "E12") (pin "4") (pinfunction "R2_4") (pintype "output"))
    )
    (net (code "90") (name "unconnected-(E12A-R3-Pad7)") (class "Default")
      (node (ref "E12") (pin "7") (pinfunction "R3_7") (pintype "output"))
    )
    (net (code "91") (name "unconnected-(E12A-R4-Pad9)") (class "Default")
      (node (ref "E12") (pin "9") (pinfunction "R4_9") (pintype "output"))
    )
  )
)
